# LCDClock.net
KiCad netlist of a schematic drawn in EAGLE
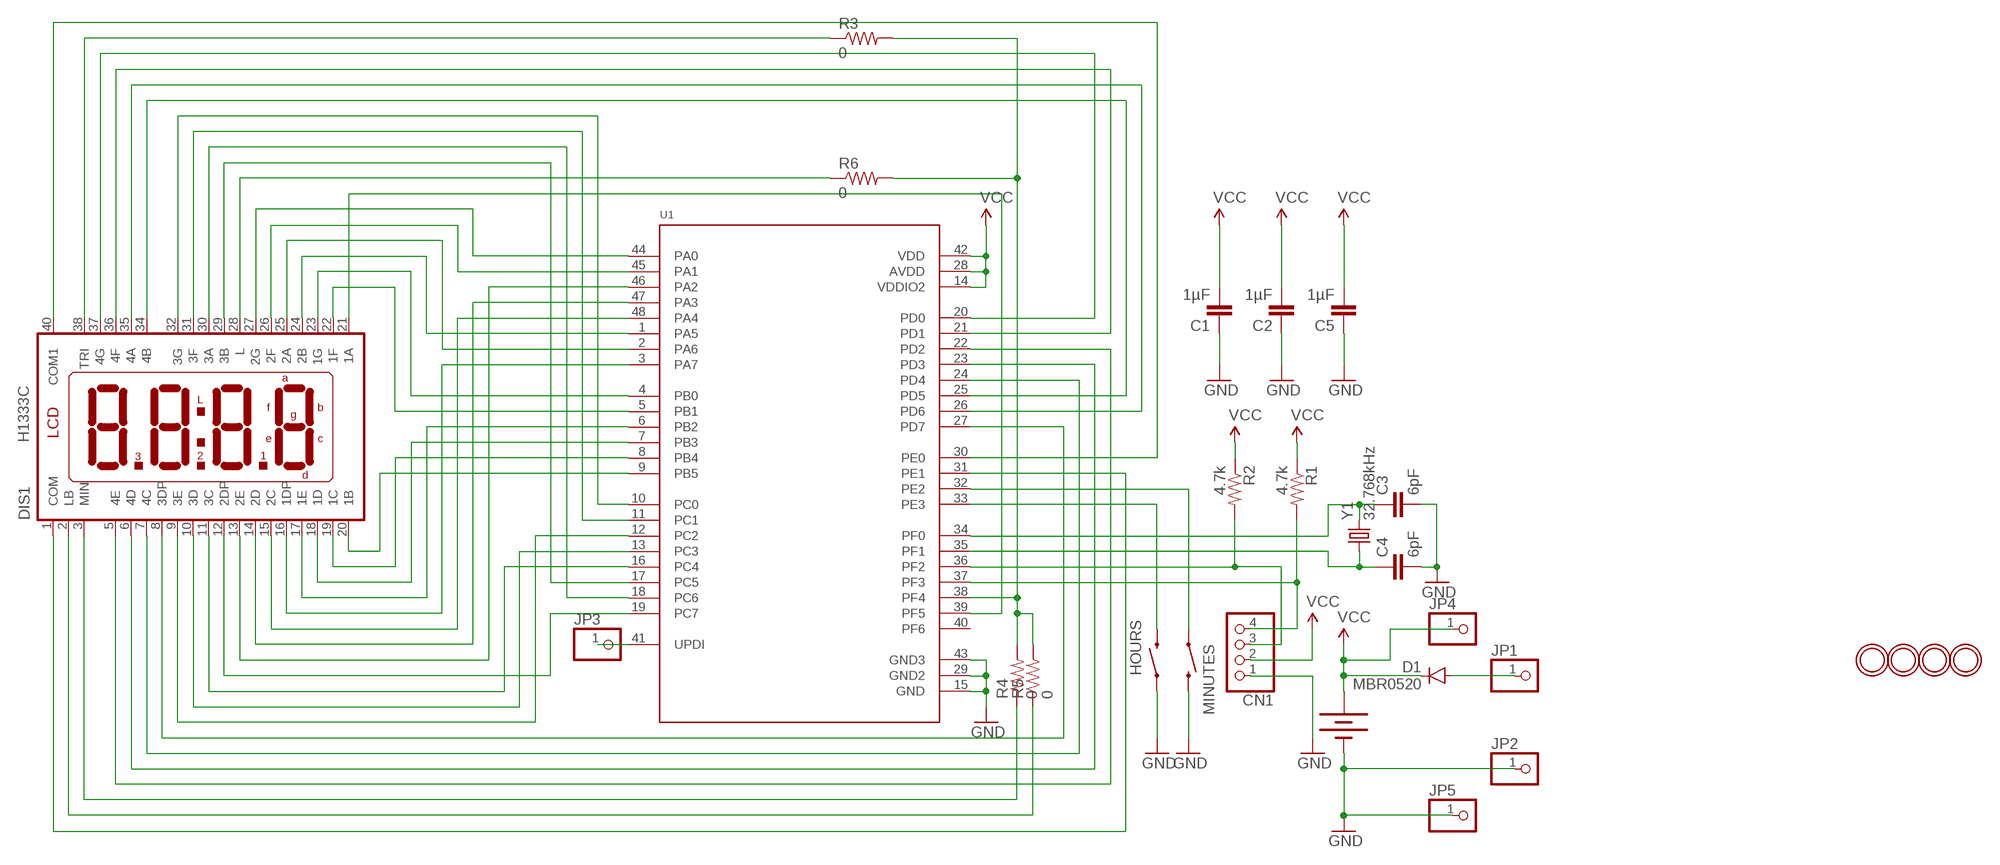
[diagram p0: schematic, sheet 1]

(export (version "E")
  (design (tool "Eeschema 10.0.6"))
  (components
    (comp (ref "BAT1")
      (value "20mm coincell")
      (footprint "eagle-import:BATTCON_20MM_4LEGS")
      (libsource (lib "eagle-import") (part "BATTERY20MM_4LEGS"))
    )
    (comp (ref "C1")
      (value "1µF")
      (footprint "eagle-import:0805")
      (libsource (lib "eagle-import") (part "CAP0805"))
    )
    (comp (ref "C2")
      (value "1µF")
      (footprint "eagle-import:0805")
      (libsource (lib "eagle-import") (part "CAP0805"))
    )
    (comp (ref "C3")
      (value "6pF")
      (footprint "eagle-import:0805")
      (libsource (lib "eagle-import") (part "CAP0805"))
    )
    (comp (ref "C4")
      (value "6pF")
      (footprint "eagle-import:0805")
      (libsource (lib "eagle-import") (part "CAP0805"))
    )
    (comp (ref "C5")
      (value "1µF")
      (footprint "eagle-import:0805")
      (libsource (lib "eagle-import") (part "CAP0805"))
    )
    (comp (ref "CN1")
      (value "JST_4PIN")
      (footprint "eagle-import:JSTPH4")
      (libsource (lib "eagle-import") (part "JST_4PIN"))
    )
    (comp (ref "D1")
      (value "MBR0520")
      (footprint "eagle-import:SOD-123")
      (libsource (lib "eagle-import") (part "DIODESOD123"))
    )
    (comp (ref "DIS1")
      (value "H1333C")
      (footprint "eagle-import:H1333C")
      (libsource (lib "eagle-import") (part "H1333C"))
    )
    (comp (ref "HOURS")
      (value "SWITCH-MOMENTARY-2SMD-4")
      (footprint "eagle-import:TACTILE_SWITCH_TALL")
      (libsource (lib "eagle-import") (part "SWITCH-MOMENTARY-2SMD-4"))
    )
    (comp (ref "JP1")
      (value "HEADER-1X1ROUND")
      (footprint "eagle-import:1X01_ROUND")
      (libsource (lib "eagle-import") (part "HEADER-1X1ROUND"))
    )
    (comp (ref "JP2")
      (value "HEADER-1X1ROUND")
      (footprint "eagle-import:1X01_ROUND")
      (libsource (lib "eagle-import") (part "HEADER-1X1ROUND"))
    )
    (comp (ref "JP3")
      (value "HEADER-1X1ROUND")
      (footprint "eagle-import:1X01_ROUND")
      (libsource (lib "eagle-import") (part "HEADER-1X1ROUND"))
    )
    (comp (ref "JP4")
      (value "HEADER-1X12MM")
      (footprint "eagle-import:1X01_2MM")
      (libsource (lib "eagle-import") (part "HEADER-1X12MM"))
    )
    (comp (ref "JP5")
      (value "HEADER-1X12MM")
      (footprint "eagle-import:1X01_2MM")
      (libsource (lib "eagle-import") (part "HEADER-1X12MM"))
    )
    (comp (ref "MINUTES")
      (value "SWITCH-MOMENTARY-2SMD-4")
      (footprint "eagle-import:TACTILE_SWITCH_TALL")
      (libsource (lib "eagle-import") (part "SWITCH-MOMENTARY-2SMD-4"))
    )
    (comp (ref "R1")
      (value "4.7k")
      (footprint "eagle-import:0805")
      (libsource (lib "eagle-import") (part "0.3OHM-1/8W-1%(0805)"))
    )
    (comp (ref "R2")
      (value "4.7k")
      (footprint "eagle-import:0805")
      (libsource (lib "eagle-import") (part "0.3OHM-1/8W-1%(0805)"))
    )
    (comp (ref "R3")
      (value "0")
      (footprint "eagle-import:0805")
      (libsource (lib "eagle-import") (part "0.3OHM-1/8W-1%(0805)"))
    )
    (comp (ref "R4")
      (value "0")
      (footprint "eagle-import:0805")
      (libsource (lib "eagle-import") (part "0.3OHM-1/8W-1%(0805)"))
    )
    (comp (ref "R5")
      (value "0")
      (footprint "eagle-import:0805")
      (libsource (lib "eagle-import") (part "0.3OHM-1/8W-1%(0805)"))
    )
    (comp (ref "R6")
      (value "0")
      (footprint "eagle-import:0805")
      (libsource (lib "eagle-import") (part "0.3OHM-1/8W-1%(0805)"))
    )
    (comp (ref "U$1")
      (value "MOUNTINGHOLE2.5")
      (footprint "eagle-import:MOUNTINGHOLE_2.5_PLATED")
      (libsource (lib "eagle-import") (part "MOUNTINGHOLE2.5"))
    )
    (comp (ref "U$4")
      (value "MOUNTINGHOLE2.5")
      (footprint "eagle-import:MOUNTINGHOLE_2.5_PLATED")
      (libsource (lib "eagle-import") (part "MOUNTINGHOLE2.5"))
    )
    (comp (ref "U$5")
      (value "MOUNTINGHOLE2.5")
      (footprint "eagle-import:MOUNTINGHOLE_2.5_PLATED")
      (libsource (lib "eagle-import") (part "MOUNTINGHOLE2.5"))
    )
    (comp (ref "U$9")
      (value "MOUNTINGHOLE2.5")
      (footprint "eagle-import:MOUNTINGHOLE_2.5_PLATED")
      (libsource (lib "eagle-import") (part "MOUNTINGHOLE2.5"))
    )
    (comp (ref "U1")
      (value "AVR128DB48")
      (footprint "eagle-import:LQFP48")
      (fields (field (name "MANF") "NXP"))
      (libsource (lib "eagle-import") (part "AVR128DB48"))
    )
    (comp (ref "Y1")
      (value "32.768kHz")
      (footprint "eagle-import:CRYSTAL-SMD-3.2X1.5MM")
      (libsource (lib "eagle-import") (part "CRYSTAL3.2X1.5MM"))
    )
  )
  (nets
    (net (code "1") (name "GND") (class "Default")
      (node (ref "BAT1") (pin "NEGATIVE") (pinfunction "-_NEGATIVE") (pintype "power_in"))
      (node (ref "C1") (pin "1") (pinfunction "1_1") (pintype "passive"))
      (node (ref "C2") (pin "1") (pinfunction "1_1") (pintype "passive"))
      (node (ref "C3") (pin "2") (pinfunction "2_2") (pintype "passive"))
      (node (ref "C4") (pin "2") (pinfunction "2_2") (pintype "passive"))
      (node (ref "C5") (pin "1") (pinfunction "1_1") (pintype "passive"))
      (node (ref "CN1") (pin "1") (pinfunction "1_1") (pintype "passive"))
      (node (ref "HOURS") (pin "A2") (pinfunction "1_A2") (pintype "passive"))
      (node (ref "JP2") (pin "1") (pinfunction "1_1") (pintype "passive"))
      (node (ref "JP5") (pin "1") (pinfunction "1_1") (pintype "passive"))
      (node (ref "MINUTES") (pin "B2") (pinfunction "2_B2") (pintype "passive"))
      (node (ref "U1") (pin "15") (pinfunction "GND_15") (pintype "power_in"))
      (node (ref "U1") (pin "29") (pinfunction "GND2_29") (pintype "power_in"))
      (node (ref "U1") (pin "43") (pinfunction "GND3_43") (pintype "power_in"))
    )
    (net (code "2") (name "Net-(D1-PadA)") (class "Default")
      (node (ref "D1") (pin "A") (pinfunction "A_A") (pintype "passive"))
      (node (ref "JP1") (pin "1") (pinfunction "1_1") (pintype "passive"))
    )
    (net (code "3") (name "Net-(DIS1-1A)") (class "Default")
      (node (ref "DIS1") (pin "21") (pinfunction "1A_21") (pintype "passive"))
      (node (ref "U1") (pin "39") (pinfunction "PF5_39") (pintype "bidirectional"))
    )
    (net (code "4") (name "Net-(DIS1-1B)") (class "Default")
      (node (ref "DIS1") (pin "20") (pinfunction "1B_20") (pintype "passive"))
      (node (ref "U1") (pin "9") (pinfunction "PB5_9") (pintype "bidirectional"))
    )
    (net (code "5") (name "Net-(DIS1-1C)") (class "Default")
      (node (ref "DIS1") (pin "19") (pinfunction "1C_19") (pintype "passive"))
      (node (ref "U1") (pin "8") (pinfunction "PB4_8") (pintype "bidirectional"))
    )
    (net (code "6") (name "Net-(DIS1-1D)") (class "Default")
      (node (ref "DIS1") (pin "18") (pinfunction "1D_18") (pintype "passive"))
      (node (ref "U1") (pin "7") (pinfunction "PB3_7") (pintype "bidirectional"))
    )
    (net (code "7") (name "Net-(DIS1-1DP)") (class "Default")
      (node (ref "DIS1") (pin "16") (pinfunction "1DP_16") (pintype "passive"))
      (node (ref "U1") (pin "3") (pinfunction "PA7_3") (pintype "bidirectional"))
    )
    (net (code "8") (name "Net-(DIS1-1E)") (class "Default")
      (node (ref "DIS1") (pin "17") (pinfunction "1E_17") (pintype "passive"))
      (node (ref "U1") (pin "6") (pinfunction "PB2_6") (pintype "output"))
    )
    (net (code "9") (name "Net-(DIS1-1F)") (class "Default")
      (node (ref "DIS1") (pin "22") (pinfunction "1F_22") (pintype "passive"))
      (node (ref "U1") (pin "5") (pinfunction "PB1_5") (pintype "bidirectional"))
    )
    (net (code "10") (name "Net-(DIS1-1G)") (class "Default")
      (node (ref "DIS1") (pin "23") (pinfunction "1G_23") (pintype "passive"))
      (node (ref "U1") (pin "4") (pinfunction "PB0_4") (pintype "bidirectional"))
    )
    (net (code "11") (name "Net-(DIS1-2A)") (class "Default")
      (node (ref "DIS1") (pin "25") (pinfunction "2A_25") (pintype "passive"))
      (node (ref "U1") (pin "2") (pinfunction "PA6_2") (pintype "bidirectional"))
    )
    (net (code "12") (name "Net-(DIS1-2B)") (class "Default")
      (node (ref "DIS1") (pin "24") (pinfunction "2B_24") (pintype "passive"))
      (node (ref "U1") (pin "1") (pinfunction "PA5_1") (pintype "bidirectional"))
    )
    (net (code "13") (name "Net-(DIS1-2C)") (class "Default")
      (node (ref "DIS1") (pin "15") (pinfunction "2C_15") (pintype "passive"))
      (node (ref "U1") (pin "48") (pinfunction "PA4_48") (pintype "bidirectional"))
    )
    (net (code "14") (name "Net-(DIS1-2D)") (class "Default")
      (node (ref "DIS1") (pin "14") (pinfunction "2D_14") (pintype "passive"))
      (node (ref "U1") (pin "47") (pinfunction "PA3_47") (pintype "bidirectional"))
    )
    (net (code "15") (name "Net-(DIS1-2DP)") (class "Default")
      (node (ref "DIS1") (pin "12") (pinfunction "2DP_12") (pintype "passive"))
      (node (ref "U1") (pin "19") (pinfunction "PC7_19") (pintype "bidirectional"))
    )
    (net (code "16") (name "Net-(DIS1-2E)") (class "Default")
      (node (ref "DIS1") (pin "13") (pinfunction "2E_13") (pintype "passive"))
      (node (ref "U1") (pin "46") (pinfunction "PA2_46") (pintype "bidirectional"))
    )
    (net (code "17") (name "Net-(DIS1-2F)") (class "Default")
      (node (ref "DIS1") (pin "26") (pinfunction "2F_26") (pintype "passive"))
      (node (ref "U1") (pin "45") (pinfunction "PA1_45") (pintype "bidirectional"))
    )
    (net (code "18") (name "Net-(DIS1-2G)") (class "Default")
      (node (ref "DIS1") (pin "27") (pinfunction "2G_27") (pintype "passive"))
      (node (ref "U1") (pin "44") (pinfunction "PA0_44") (pintype "bidirectional"))
    )
    (net (code "19") (name "Net-(DIS1-3A)") (class "Default")
      (node (ref "DIS1") (pin "30") (pinfunction "3A_30") (pintype "passive"))
      (node (ref "U1") (pin "18") (pinfunction "PC6_18") (pintype "bidirectional"))
    )
    (net (code "20") (name "Net-(DIS1-3B)") (class "Default")
      (node (ref "DIS1") (pin "29") (pinfunction "3B_29") (pintype "passive"))
      (node (ref "U1") (pin "17") (pinfunction "PC5_17") (pintype "bidirectional"))
    )
    (net (code "21") (name "Net-(DIS1-3C)") (class "Default")
      (node (ref "DIS1") (pin "11") (pinfunction "3C_11") (pintype "passive"))
      (node (ref "U1") (pin "16") (pinfunction "PC4_16") (pintype "bidirectional"))
    )
    (net (code "22") (name "Net-(DIS1-3D)") (class "Default")
      (node (ref "DIS1") (pin "10") (pinfunction "3D_10") (pintype "passive"))
      (node (ref "U1") (pin "13") (pinfunction "PC3_13") (pintype "bidirectional"))
    )
    (net (code "23") (name "Net-(DIS1-3DP)") (class "Default")
      (node (ref "DIS1") (pin "8") (pinfunction "3DP_8") (pintype "passive"))
      (node (ref "U1") (pin "27") (pinfunction "PD7_27") (pintype "bidirectional"))
    )
    (net (code "24") (name "Net-(DIS1-3E)") (class "Default")
      (node (ref "DIS1") (pin "9") (pinfunction "3E_9") (pintype "passive"))
      (node (ref "U1") (pin "12") (pinfunction "PC2_12") (pintype "bidirectional"))
    )
    (net (code "25") (name "Net-(DIS1-3F)") (class "Default")
      (node (ref "DIS1") (pin "31") (pinfunction "3F_31") (pintype "passive"))
      (node (ref "U1") (pin "11") (pinfunction "PC1_11") (pintype "bidirectional"))
    )
    (net (code "26") (name "Net-(DIS1-3G)") (class "Default")
      (node (ref "DIS1") (pin "32") (pinfunction "3G_32") (pintype "passive"))
      (node (ref "U1") (pin "10") (pinfunction "PC0_10") (pintype "bidirectional"))
    )
    (net (code "27") (name "Net-(DIS1-4A)") (class "Default")
      (node (ref "DIS1") (pin "35") (pinfunction "4A_35") (pintype "passive"))
      (node (ref "U1") (pin "26") (pinfunction "PD6_26") (pintype "bidirectional"))
    )
    (net (code "28") (name "Net-(DIS1-4B)") (class "Default")
      (node (ref "DIS1") (pin "34") (pinfunction "4B_34") (pintype "passive"))
      (node (ref "U1") (pin "25") (pinfunction "PD5_25") (pintype "bidirectional"))
    )
    (net (code "29") (name "Net-(DIS1-4C)") (class "Default")
      (node (ref "DIS1") (pin "7") (pinfunction "4C_7") (pintype "passive"))
      (node (ref "U1") (pin "24") (pinfunction "PD4_24") (pintype "bidirectional"))
    )
    (net (code "30") (name "Net-(DIS1-4D)") (class "Default")
      (node (ref "DIS1") (pin "6") (pinfunction "4D_6") (pintype "passive"))
      (node (ref "U1") (pin "23") (pinfunction "PD3_23") (pintype "bidirectional"))
    )
    (net (code "31") (name "Net-(DIS1-4E)") (class "Default")
      (node (ref "DIS1") (pin "5") (pinfunction "4E_5") (pintype "passive"))
      (node (ref "U1") (pin "22") (pinfunction "PD2_22") (pintype "bidirectional"))
    )
    (net (code "32") (name "Net-(DIS1-4F)") (class "Default")
      (node (ref "DIS1") (pin "36") (pinfunction "4F_36") (pintype "passive"))
      (node (ref "U1") (pin "21") (pinfunction "PD1_21") (pintype "bidirectional"))
    )
    (net (code "33") (name "Net-(DIS1-4G)") (class "Default")
      (node (ref "DIS1") (pin "37") (pinfunction "4G_37") (pintype "passive"))
      (node (ref "U1") (pin "20") (pinfunction "PD0_20") (pintype "bidirectional"))
    )
    (net (code "34") (name "Net-(DIS1-COM)") (class "Default")
      (node (ref "DIS1") (pin "1") (pinfunction "COM_1") (pintype "passive"))
      (node (ref "U1") (pin "31") (pinfunction "PE1_31") (pintype "bidirectional"))
    )
    (net (code "35") (name "Net-(DIS1-COM1)") (class "Default")
      (node (ref "DIS1") (pin "40") (pinfunction "COM1_40") (pintype "passive"))
      (node (ref "U1") (pin "30") (pinfunction "PE0_30") (pintype "bidirectional"))
    )
    (net (code "36") (name "Net-(DIS1-L)") (class "Default")
      (node (ref "DIS1") (pin "28") (pinfunction "L_28") (pintype "passive"))
      (node (ref "R6") (pin "1") (pinfunction "1_1") (pintype "passive"))
    )
    (net (code "37") (name "Net-(DIS1-LB)") (class "Default")
      (node (ref "DIS1") (pin "2") (pinfunction "LB_2") (pintype "passive"))
      (node (ref "R5") (pin "1") (pinfunction "1_1") (pintype "passive"))
    )
    (net (code "38") (name "Net-(DIS1-MIN)") (class "Default")
      (node (ref "DIS1") (pin "3") (pinfunction "MIN_3") (pintype "passive"))
      (node (ref "R4") (pin "1") (pinfunction "1_1") (pintype "passive"))
    )
    (net (code "39") (name "Net-(DIS1-TRI)") (class "Default")
      (node (ref "DIS1") (pin "38") (pinfunction "TRI_38") (pintype "passive"))
      (node (ref "R3") (pin "1") (pinfunction "1_1") (pintype "passive"))
    )
    (net (code "40") (name "Net-(HOURS-2)") (class "Default")
      (node (ref "HOURS") (pin "B2") (pinfunction "2_B2") (pintype "passive"))
      (node (ref "U1") (pin "33") (pinfunction "PE3_33") (pintype "bidirectional"))
    )
    (net (code "41") (name "Net-(MINUTES-1)") (class "Default")
      (node (ref "MINUTES") (pin "A2") (pinfunction "1_A2") (pintype "passive"))
      (node (ref "U1") (pin "32") (pinfunction "PE2_32") (pintype "bidirectional"))
    )
    (net (code "42") (name "Net-(U1-PF0)") (class "Default")
      (node (ref "C3") (pin "1") (pinfunction "1_1") (pintype "passive"))
      (node (ref "U1") (pin "34") (pinfunction "PF0_34") (pintype "bidirectional"))
      (node (ref "Y1") (pin "P$2") (pinfunction "2_P$2") (pintype "passive"))
    )
    (net (code "43") (name "Net-(U1-PF1)") (class "Default")
      (node (ref "C4") (pin "1") (pinfunction "1_1") (pintype "passive"))
      (node (ref "U1") (pin "35") (pinfunction "PF1_35") (pintype "bidirectional"))
      (node (ref "Y1") (pin "P$1") (pinfunction "1_P$1") (pintype "passive"))
    )
    (net (code "44") (name "Net-(U1-PF2)") (class "Default")
      (node (ref "CN1") (pin "3") (pinfunction "3_3") (pintype "passive"))
      (node (ref "R2") (pin "2") (pinfunction "2_2") (pintype "passive"))
      (node (ref "U1") (pin "36") (pinfunction "PF2_36") (pintype "bidirectional"))
    )
    (net (code "45") (name "Net-(U1-PF3)") (class "Default")
      (node (ref "CN1") (pin "4") (pinfunction "4_4") (pintype "passive"))
      (node (ref "R1") (pin "2") (pinfunction "2_2") (pintype "passive"))
      (node (ref "U1") (pin "37") (pinfunction "PF3_37") (pintype "bidirectional"))
    )
    (net (code "46") (name "Net-(U1-PF4)") (class "Default")
      (node (ref "R3") (pin "2") (pinfunction "2_2") (pintype "passive"))
      (node (ref "R4") (pin "2") (pinfunction "2_2") (pintype "passive"))
      (node (ref "R5") (pin "2") (pinfunction "2_2") (pintype "passive"))
      (node (ref "R6") (pin "2") (pinfunction "2_2") (pintype "passive"))
      (node (ref "U1") (pin "38") (pinfunction "PF4_38") (pintype "bidirectional"))
    )
    (net (code "47") (name "Net-(U1-UPDI)") (class "Default")
      (node (ref "JP3") (pin "1") (pinfunction "1_1") (pintype "passive"))
      (node (ref "U1") (pin "41") (pinfunction "UPDI_41") (pintype "bidirectional"))
    )
    (net (code "48") (name "VCC") (class "Default")
      (node (ref "BAT1") (pin "POSITIVE@1") (pinfunction "+_POSITIVE@1") (pintype "power_in"))
      (node (ref "BAT1") (pin "POSITIVE@2") (pinfunction "+_POSITIVE@2") (pintype "power_in"))
      (node (ref "BAT1") (pin "POSITIVE@3") (pinfunction "+_POSITIVE@3") (pintype "power_in"))
      (node (ref "BAT1") (pin "POSITIVE@4") (pinfunction "+_POSITIVE@4") (pintype "power_in"))
      (node (ref "C1") (pin "2") (pinfunction "2_2") (pintype "passive"))
      (node (ref "C2") (pin "2") (pinfunction "2_2") (pintype "passive"))
      (node (ref "C5") (pin "2") (pinfunction "2_2") (pintype "passive"))
      (node (ref "CN1") (pin "2") (pinfunction "2_2") (pintype "passive"))
      (node (ref "D1") (pin "C") (pinfunction "C_C") (pintype "passive"))
      (node (ref "JP4") (pin "1") (pinfunction "1_1") (pintype "passive"))
      (node (ref "R1") (pin "1") (pinfunction "1_1") (pintype "passive"))
      (node (ref "R2") (pin "1") (pinfunction "1_1") (pintype "passive"))
      (node (ref "U1") (pin "14") (pinfunction "VDDIO2_14") (pintype "power_in"))
      (node (ref "U1") (pin "28") (pinfunction "AVDD_28") (pintype "power_in"))
      (node (ref "U1") (pin "42") (pinfunction "VDD_42") (pintype "power_in"))
    )
    (net (code "49") (name "unconnected-(U1-PF6-Pad40)") (class "Default")
      (node (ref "U1") (pin "40") (pinfunction "PF6_40") (pintype "bidirectional"))
    )
  )
)
